# 0-10V_Converter.net
KiCad netlist of a schematic drawn in Altium Designer
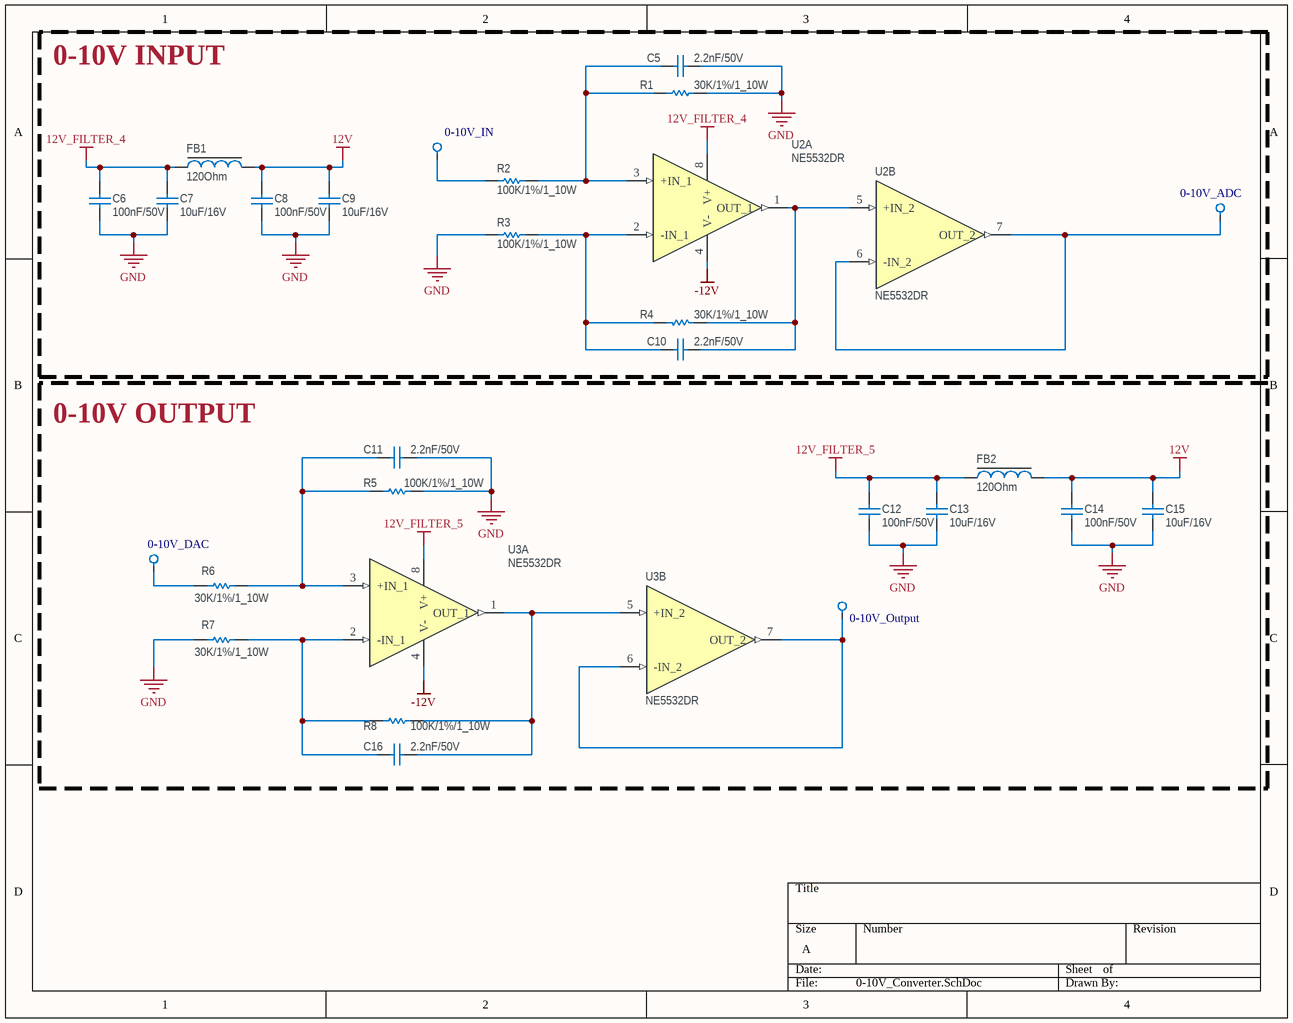
[diagram p0: 0-10V_Converter.SchDoc]

(export (version "E")
  (design (tool "Eeschema 10.0.6"))
  (components
    (comp (ref "0-10V_ADC")
      (value "0-10V_ADC")
      (footprint "TestPoint_THTPad_D1.5mm_Drill0.7mm")
      (description "Test Point TEST-1BK")
      (libsource (lib "BluetoothTracking") (part "Testpoint_TH"))
    )
    (comp (ref "0-10V_DAC")
      (value "0-10V_DAC")
      (footprint "TestPoint_THTPad_D1.5mm_Drill0.7mm")
      (description "Test Point TEST-1BK")
      (libsource (lib "BluetoothTracking") (part "Testpoint_TH"))
    )
    (comp (ref "0-10V_IN")
      (value "0-10V_IN")
      (footprint "TestPoint_THTPad_D1.5mm_Drill0.7mm")
      (description "Test Point TEST-1BK")
      (libsource (lib "BluetoothTracking") (part "Testpoint_TH"))
    )
    (comp (ref "0-10V_Output")
      (value "0-10V_Output")
      (footprint "TestPoint_THTPad_D1.5mm_Drill0.7mm")
      (description "Test Point TEST-1BK")
      (libsource (lib "BluetoothTracking") (part "Testpoint_TH"))
    )
    (comp (ref "C5")
      (value "2.2nF/50V")
      (footprint "CAP_0603")
      (description "CAP, size 0603, 2.2nF, 50V")
      (fields (field (name "SUPPLY PART NUMBER") "CC0603KRX7R9BB222"))
      (libsource (lib "BluetoothTracking") (part "Ceramic_Cap_2.2nF_50V_0603"))
    )
    (comp (ref "C6")
      (value "100nF/50V")
      (footprint "CAP_0603")
      (description "CAP, size 0603, 100nF, 50V")
      (fields (field (name "SUPPLY PART NUMBER") "Tụ Gốm 0603 100nF (0.1uF) 50V"))
      (libsource (lib "BluetoothTracking") (part "Ceramic_Cap_100nF_50V_0603"))
    )
    (comp (ref "C7")
      (value "10uF/16V")
      (footprint "CAP_0603")
      (description "CAP, size 0603, 10uF, 16V")
      (fields (field (name "SUPPLY PART NUMBER") "Tụ Gốm 0603 10uF 16V"))
      (libsource (lib "BluetoothTracking") (part "Ceramic_Cap_10uF_16V_0603"))
    )
    (comp (ref "C8")
      (value "100nF/50V")
      (footprint "CAP_0603")
      (description "CAP, size 0603, 100nF, 50V")
      (fields (field (name "SUPPLY PART NUMBER") "Tụ Gốm 0603 100nF (0.1uF) 50V"))
      (libsource (lib "BluetoothTracking") (part "Ceramic_Cap_100nF_50V_0603"))
    )
    (comp (ref "C9")
      (value "10uF/16V")
      (footprint "CAP_0603")
      (description "CAP, size 0603, 10uF, 16V")
      (fields (field (name "SUPPLY PART NUMBER") "Tụ Gốm 0603 10uF 16V"))
      (libsource (lib "BluetoothTracking") (part "Ceramic_Cap_10uF_16V_0603"))
    )
    (comp (ref "C10")
      (value "2.2nF/50V")
      (footprint "CAP_0603")
      (description "CAP, size 0603, 2.2nF, 50V")
      (fields (field (name "SUPPLY PART NUMBER") "CC0603KRX7R9BB222"))
      (libsource (lib "BluetoothTracking") (part "Ceramic_Cap_2.2nF_50V_0603"))
    )
    (comp (ref "C11")
      (value "2.2nF/50V")
      (footprint "CAP_0603")
      (description "CAP, size 0603, 2.2nF, 50V")
      (fields (field (name "SUPPLY PART NUMBER") "CC0603KRX7R9BB222"))
      (libsource (lib "BluetoothTracking") (part "Ceramic_Cap_2.2nF_50V_0603"))
    )
    (comp (ref "C12")
      (value "100nF/50V")
      (footprint "CAP_0603")
      (description "CAP, size 0603, 100nF, 50V")
      (fields (field (name "SUPPLY PART NUMBER") "Tụ Gốm 0603 100nF (0.1uF) 50V"))
      (libsource (lib "BluetoothTracking") (part "Ceramic_Cap_100nF_50V_0603"))
    )
    (comp (ref "C13")
      (value "10uF/16V")
      (footprint "CAP_0603")
      (description "CAP, size 0603, 10uF, 16V")
      (fields (field (name "SUPPLY PART NUMBER") "Tụ Gốm 0603 10uF 16V"))
      (libsource (lib "BluetoothTracking") (part "Ceramic_Cap_10uF_16V_0603"))
    )
    (comp (ref "C14")
      (value "100nF/50V")
      (footprint "CAP_0603")
      (description "CAP, size 0603, 100nF, 50V")
      (fields (field (name "SUPPLY PART NUMBER") "Tụ Gốm 0603 100nF (0.1uF) 50V"))
      (libsource (lib "BluetoothTracking") (part "Ceramic_Cap_100nF_50V_0603"))
    )
    (comp (ref "C15")
      (value "10uF/16V")
      (footprint "CAP_0603")
      (description "CAP, size 0603, 10uF, 16V")
      (fields (field (name "SUPPLY PART NUMBER") "Tụ Gốm 0603 10uF 16V"))
      (libsource (lib "BluetoothTracking") (part "Ceramic_Cap_10uF_16V_0603"))
    )
    (comp (ref "C16")
      (value "2.2nF/50V")
      (footprint "CAP_0603")
      (description "CAP, size 0603, 2.2nF, 50V")
      (fields (field (name "SUPPLY PART NUMBER") "CC0603KRX7R9BB222"))
      (libsource (lib "BluetoothTracking") (part "Ceramic_Cap_2.2nF_50V_0603"))
    )
    (comp (ref "FB1")
      (value "120Ohm")
      (footprint "Ferrite_Bead_0805")
      (description "Ferrite Bead, size 0805, 120Ohm, 2A")
      (fields (field (name "SUPPLY PART NUMBER") "CBW201209U121T Ferrite Beads 2A 120 Ohm 0805"))
      (libsource (lib "BluetoothTracking") (part "Ferrite_Bead_120Ohm_2A_0805"))
    )
    (comp (ref "FB2")
      (value "120Ohm")
      (footprint "Ferrite_Bead_0805")
      (description "Ferrite Bead, size 0805, 120Ohm, 2A")
      (fields (field (name "SUPPLY PART NUMBER") "CBW201209U121T Ferrite Beads 2A 120 Ohm 0805"))
      (libsource (lib "BluetoothTracking") (part "Ferrite_Bead_120Ohm_2A_0805"))
    )
    (comp (ref "R1")
      (value "30K/1%/1_10W")
      (footprint "Resistor_0603")
      (description "Resistor 0603 30KOhm 1% 1_10W")
      (fields (field (name "SUPPLY PART NUMBER") "Điện Trở 30 KOhm 0603 1%"))
      (libsource (lib "BluetoothTracking") (part "Res_30K_0603_1%"))
    )
    (comp (ref "R2")
      (value "100K/1%/1_10W")
      (footprint "Resistor_0603")
      (description "Resistor 0603 100KOhm 1% 1_10W")
      (fields (field (name "SUPPLY PART NUMBER") "Điện Trở 100 KOhm 0603 1%"))
      (libsource (lib "BluetoothTracking") (part "Res_100K_0603_1%"))
    )
    (comp (ref "R3")
      (value "100K/1%/1_10W")
      (footprint "Resistor_0603")
      (description "Resistor 0603 100KOhm 1% 1_10W")
      (fields (field (name "SUPPLY PART NUMBER") "Điện Trở 100 KOhm 0603 1%"))
      (libsource (lib "BluetoothTracking") (part "Res_100K_0603_1%"))
    )
    (comp (ref "R4")
      (value "30K/1%/1_10W")
      (footprint "Resistor_0603")
      (description "Resistor 0603 30KOhm 1% 1_10W")
      (fields (field (name "SUPPLY PART NUMBER") "Điện Trở 30 KOhm 0603 1%"))
      (libsource (lib "BluetoothTracking") (part "Res_30K_0603_1%"))
    )
    (comp (ref "R5")
      (value "100K/1%/1_10W")
      (footprint "Resistor_0603")
      (description "Resistor 0603 100KOhm 1% 1_10W")
      (fields (field (name "SUPPLY PART NUMBER") "Điện Trở 100 KOhm 0603 1%"))
      (libsource (lib "BluetoothTracking") (part "Res_100K_0603_1%"))
    )
    (comp (ref "R6")
      (value "30K/1%/1_10W")
      (footprint "Resistor_0603")
      (description "Resistor 0603 30KOhm 1% 1_10W")
      (fields (field (name "SUPPLY PART NUMBER") "Điện Trở 30 KOhm 0603 1%"))
      (libsource (lib "BluetoothTracking") (part "Res_30K_0603_1%"))
    )
    (comp (ref "R7")
      (value "30K/1%/1_10W")
      (footprint "Resistor_0603")
      (description "Resistor 0603 30KOhm 1% 1_10W")
      (fields (field (name "SUPPLY PART NUMBER") "Điện Trở 30 KOhm 0603 1%"))
      (libsource (lib "BluetoothTracking") (part "Res_30K_0603_1%"))
    )
    (comp (ref "R8")
      (value "100K/1%/1_10W")
      (footprint "Resistor_0603")
      (description "Resistor 0603 100KOhm 1% 1_10W")
      (fields (field (name "SUPPLY PART NUMBER") "Điện Trở 100 KOhm 0603 1%"))
      (libsource (lib "BluetoothTracking") (part "Res_100K_0603_1%"))
    )
    (comp (ref "U2")
      (value "NE5532DR")
      (footprint "SOIC-8")
      (description "Low Noise Single/Dual Operational Amplifier - SOIC-8")
      (libsource (lib "BluetoothTracking") (part "NE5532DR"))
    )
    (comp (ref "U3")
      (value "NE5532DR")
      (footprint "SOIC-8")
      (description "Low Noise Single/Dual Operational Amplifier - SOIC-8")
      (libsource (lib "BluetoothTracking") (part "NE5532DR"))
    )
  )
  (nets
    (net (code "1") (name "-12V") (class "Default")
      (node (ref "U2") (pin "4") (pinfunction "V-_4") (pintype "power_in"))
      (node (ref "U3") (pin "4") (pinfunction "V-_4") (pintype "power_in"))
    )
    (net (code "2") (name "12V") (class "Default")
      (node (ref "C14") (pin "2") (pinfunction "2_2") (pintype "passive"))
      (node (ref "C15") (pin "2") (pinfunction "2_2") (pintype "passive"))
      (node (ref "C8") (pin "2") (pinfunction "2_2") (pintype "passive"))
      (node (ref "C9") (pin "2") (pinfunction "2_2") (pintype "passive"))
      (node (ref "FB1") (pin "2") (pinfunction "2_2") (pintype "passive"))
      (node (ref "FB2") (pin "2") (pinfunction "2_2") (pintype "passive"))
    )
    (net (code "3") (name "12V_FILTER_4") (class "Default")
      (node (ref "C6") (pin "2") (pinfunction "2_2") (pintype "passive"))
      (node (ref "C7") (pin "2") (pinfunction "2_2") (pintype "passive"))
      (node (ref "FB1") (pin "1") (pinfunction "1_1") (pintype "passive"))
      (node (ref "U2") (pin "8") (pinfunction "V+_8") (pintype "power_in"))
    )
    (net (code "4") (name "12V_FILTER_5") (class "Default")
      (node (ref "C12") (pin "2") (pinfunction "2_2") (pintype "passive"))
      (node (ref "C13") (pin "2") (pinfunction "2_2") (pintype "passive"))
      (node (ref "FB2") (pin "1") (pinfunction "1_1") (pintype "passive"))
      (node (ref "U3") (pin "8") (pinfunction "V+_8") (pintype "power_in"))
    )
    (net (code "5") (name "GND") (class "Default")
      (node (ref "C11") (pin "2") (pinfunction "2_2") (pintype "passive"))
      (node (ref "C12") (pin "1") (pinfunction "1_1") (pintype "passive"))
      (node (ref "C13") (pin "1") (pinfunction "1_1") (pintype "passive"))
      (node (ref "C14") (pin "1") (pinfunction "1_1") (pintype "passive"))
      (node (ref "C15") (pin "1") (pinfunction "1_1") (pintype "passive"))
      (node (ref "C5") (pin "2") (pinfunction "2_2") (pintype "passive"))
      (node (ref "C6") (pin "1") (pinfunction "1_1") (pintype "passive"))
      (node (ref "C7") (pin "1") (pinfunction "1_1") (pintype "passive"))
      (node (ref "C8") (pin "1") (pinfunction "1_1") (pintype "passive"))
      (node (ref "C9") (pin "1") (pinfunction "1_1") (pintype "passive"))
      (node (ref "R1") (pin "2") (pinfunction "2_2") (pintype "passive"))
      (node (ref "R3") (pin "1") (pinfunction "1_1") (pintype "passive"))
      (node (ref "R5") (pin "2") (pinfunction "2_2") (pintype "passive"))
      (node (ref "R7") (pin "1") (pinfunction "1_1") (pintype "passive"))
    )
    (net (code "6") (name "Net-(0-10V_DAC-Pad1)") (class "Default")
      (node (ref "0-10V_DAC") (pin "1") (pinfunction "1_1") (pintype "passive"))
      (node (ref "R6") (pin "1") (pinfunction "1_1") (pintype "passive"))
    )
    (net (code "7") (name "Net-(0-10V_IN-Pad1)") (class "Default")
      (node (ref "0-10V_IN") (pin "1") (pinfunction "1_1") (pintype "passive"))
      (node (ref "R2") (pin "1") (pinfunction "1_1") (pintype "passive"))
    )
    (net (code "8") (name "Net-(U2A-+IN_1)") (class "Default")
      (node (ref "C5") (pin "1") (pinfunction "1_1") (pintype "passive"))
      (node (ref "R1") (pin "1") (pinfunction "1_1") (pintype "passive"))
      (node (ref "R2") (pin "2") (pinfunction "2_2") (pintype "passive"))
      (node (ref "U2") (pin "3") (pinfunction "+IN_1_3") (pintype "input"))
    )
    (net (code "9") (name "Net-(U2A--IN_1)") (class "Default")
      (node (ref "C10") (pin "1") (pinfunction "1_1") (pintype "passive"))
      (node (ref "R3") (pin "2") (pinfunction "2_2") (pintype "passive"))
      (node (ref "R4") (pin "1") (pinfunction "1_1") (pintype "passive"))
      (node (ref "U2") (pin "2") (pinfunction "-IN_1_2") (pintype "input"))
    )
    (net (code "10") (name "Net-(U2A-OUT_1)") (class "Default")
      (node (ref "C10") (pin "2") (pinfunction "2_2") (pintype "passive"))
      (node (ref "R4") (pin "2") (pinfunction "2_2") (pintype "passive"))
      (node (ref "U2") (pin "1") (pinfunction "OUT_1_1") (pintype "output"))
      (node (ref "U2") (pin "5") (pinfunction "+IN_2_5") (pintype "input"))
    )
    (net (code "11") (name "Net-(U2B--IN_2)") (class "Default")
      (node (ref "0-10V_ADC") (pin "1") (pinfunction "1_1") (pintype "passive"))
      (node (ref "U2") (pin "6") (pinfunction "-IN_2_6") (pintype "input"))
      (node (ref "U2") (pin "7") (pinfunction "OUT_2_7") (pintype "output"))
    )
    (net (code "12") (name "Net-(U3A-+IN_1)") (class "Default")
      (node (ref "C11") (pin "1") (pinfunction "1_1") (pintype "passive"))
      (node (ref "R5") (pin "1") (pinfunction "1_1") (pintype "passive"))
      (node (ref "R6") (pin "2") (pinfunction "2_2") (pintype "passive"))
      (node (ref "U3") (pin "3") (pinfunction "+IN_1_3") (pintype "input"))
    )
    (net (code "13") (name "Net-(U3A--IN_1)") (class "Default")
      (node (ref "C16") (pin "1") (pinfunction "1_1") (pintype "passive"))
      (node (ref "R7") (pin "2") (pinfunction "2_2") (pintype "passive"))
      (node (ref "R8") (pin "1") (pinfunction "1_1") (pintype "passive"))
      (node (ref "U3") (pin "2") (pinfunction "-IN_1_2") (pintype "input"))
    )
    (net (code "14") (name "Net-(U3A-OUT_1)") (class "Default")
      (node (ref "C16") (pin "2") (pinfunction "2_2") (pintype "passive"))
      (node (ref "R8") (pin "2") (pinfunction "2_2") (pintype "passive"))
      (node (ref "U3") (pin "1") (pinfunction "OUT_1_1") (pintype "output"))
      (node (ref "U3") (pin "5") (pinfunction "+IN_2_5") (pintype "input"))
    )
    (net (code "15") (name "Net-(U3B--IN_2)") (class "Default")
      (node (ref "0-10V_Output") (pin "1") (pinfunction "1_1") (pintype "passive"))
      (node (ref "U3") (pin "6") (pinfunction "-IN_2_6") (pintype "input"))
      (node (ref "U3") (pin "7") (pinfunction "OUT_2_7") (pintype "output"))
    )
  )
)
